# FULL_CB_Servo_REV_C.net
KiCad netlist of a schematic drawn in Altium Designer
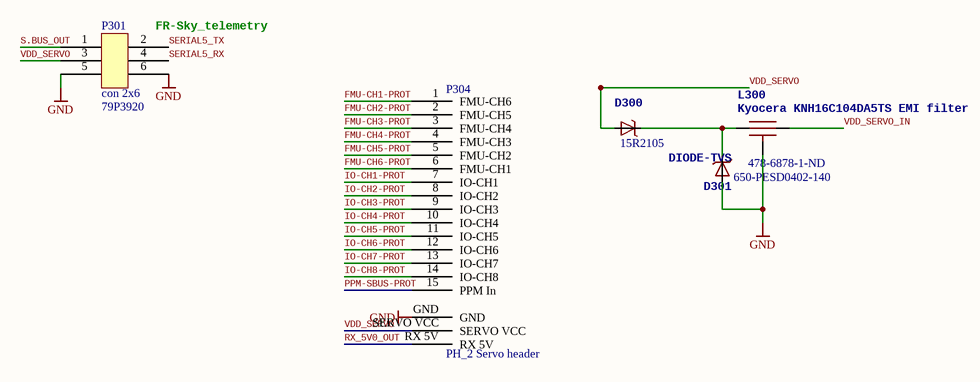
[diagram p0: FULL_CB_Servo_REV_C.SchDoc]

(export (version "E")
  (design (tool "Eeschema 10.0.6"))
  (components
    (comp (ref "D300")
      (value "MSS1P4-M3")
      (footprint "MICROSMP")
      (description "Diode, Schottky, 40V, 1A, MicroSMP, SMD")
      (fields (field (name "SUPPLIER PART NUMBER 1") "15R2105"))
      (libsource (lib "CB_REV_C") (part "DIODE-SCHOTTKY_MSMP"))
    )
    (comp (ref "D301")
      (value "DIODE-TVS")
      (footprint "0402-TVS")
      (description "Diode, TVS, 14VWM, 40VC, 0402, SMD")
      (fields (field (name "SUPPLIER PART NUMBER 1") "650-PESD0402-140"))
      (libsource (lib "CB_REV_C") (part "DIODE-TVS"))
    )
    (comp (ref "L300")
      (value "Kyocera KNH16C104DA5TS EMI filter")
      (footprint "KYOCERA-KNH16-DA")
      (description "Capacitor, Filter, 0.1uF, 25V, 2A, 0603, SMD")
      (fields (field (name "SUPPLIER PART NUMBER 1") "478-6878-1-ND"))
      (libsource (lib "CB_REV_C") (part "KNH16C104DA5TS"))
    )
    (comp (ref "P301")
      (value "con 2x6")
      (footprint "TSW-103-07-G-D")
      (description "Connector, Header, 6Pos, 2.54MM, Vert, THT, Au")
      (fields (field (name "SUPPLIER PART NUMBER 1") "79P3920"))
      (libsource (lib "CB_REV_C") (part "con 2x6"))
    )
    (comp (ref "P304")
      (value "PH_2 Servo header")
      (footprint "TSW-115-08-G-T-RA")
      (description "Connector, Header, 45Pos, 2.54MM, R/A, THT, Tin")
      (libsource (lib "CB_REV_C") (part "PH_2 Servo header"))
    )
  )
  (nets
    (net (code "1") (name "/FMU-CH1-PROT") (class "Default")
      (node (ref "P304") (pin "1") (pinfunction "FMU-CH6_1") (pintype "passive"))
    )
    (net (code "2") (name "/FMU-CH2-PROT") (class "Default")
      (node (ref "P304") (pin "2") (pinfunction "FMU-CH5_2") (pintype "passive"))
    )
    (net (code "3") (name "/FMU-CH3-PROT") (class "Default")
      (node (ref "P304") (pin "3") (pinfunction "FMU-CH4_3") (pintype "passive"))
    )
    (net (code "4") (name "/FMU-CH4-PROT") (class "Default")
      (node (ref "P304") (pin "4") (pinfunction "FMU-CH3_4") (pintype "passive"))
    )
    (net (code "5") (name "/FMU-CH5-PROT") (class "Default")
      (node (ref "P304") (pin "5") (pinfunction "FMU-CH2_5") (pintype "passive"))
    )
    (net (code "6") (name "/FMU-CH6-PROT") (class "Default")
      (node (ref "P304") (pin "6") (pinfunction "FMU-CH1_6") (pintype "passive"))
    )
    (net (code "7") (name "/IO-CH1-PROT") (class "Default")
      (node (ref "P304") (pin "7") (pinfunction "IO-CH1_7") (pintype "passive"))
    )
    (net (code "8") (name "/IO-CH2-PROT") (class "Default")
      (node (ref "P304") (pin "8") (pinfunction "IO-CH2_8") (pintype "passive"))
    )
    (net (code "9") (name "/IO-CH3-PROT") (class "Default")
      (node (ref "P304") (pin "9") (pinfunction "IO-CH3_9") (pintype "passive"))
    )
    (net (code "10") (name "/IO-CH4-PROT") (class "Default")
      (node (ref "P304") (pin "10") (pinfunction "IO-CH4_10") (pintype "passive"))
    )
    (net (code "11") (name "/IO-CH5-PROT") (class "Default")
      (node (ref "P304") (pin "11") (pinfunction "IO-CH5_11") (pintype "passive"))
    )
    (net (code "12") (name "/IO-CH6-PROT") (class "Default")
      (node (ref "P304") (pin "12") (pinfunction "IO-CH6_12") (pintype "passive"))
    )
    (net (code "13") (name "/IO-CH7-PROT") (class "Default")
      (node (ref "P304") (pin "13") (pinfunction "IO-CH7_13") (pintype "passive"))
    )
    (net (code "14") (name "/IO-CH8-PROT") (class "Default")
      (node (ref "P304") (pin "14") (pinfunction "IO-CH8_14") (pintype "passive"))
    )
    (net (code "15") (name "/PPM-SBUS-PROT") (class "Default")
      (node (ref "P304") (pin "15") (pinfunction "PPM_In_15") (pintype "passive"))
    )
    (net (code "16") (name "/RX_5V0_OUT") (class "Default")
      (node (ref "P304") (pin "RX_5V") (pinfunction "RX_5V_RX_5V") (pintype "passive"))
    )
    (net (code "17") (name "/S.BUS_OUT") (class "Default")
      (node (ref "P301") (pin "1") (pinfunction "1_1") (pintype "passive"))
    )
    (net (code "18") (name "/SERIAL5_RX") (class "Default")
      (node (ref "P301") (pin "4") (pinfunction "4_4") (pintype "passive"))
    )
    (net (code "19") (name "/SERIAL5_TX") (class "Default")
      (node (ref "P301") (pin "2") (pinfunction "2_2") (pintype "passive"))
    )
    (net (code "20") (name "/VDD_SERVO") (class "Default")
      (node (ref "D300") (pin "ANODE") (pinfunction "A_ANODE") (pintype "passive"))
      (node (ref "P301") (pin "3") (pinfunction "3_3") (pintype "passive"))
      (node (ref "P304") (pin "SERVO_VCC") (pinfunction "SERVO_VCC_SERVO_VCC") (pintype "passive"))
    )
    (net (code "21") (name "/VDD_SERVO_IN") (class "Default")
      (node (ref "L300") (pin "P$2") (pinfunction "P$2_P$2") (pintype "passive"))
    )
    (net (code "22") (name "GND") (class "Default")
      (node (ref "D301") (pin "A") (pinfunction "A_A") (pintype "passive"))
      (node (ref "L300") (pin "GND") (pinfunction "GND_GND") (pintype "passive"))
      (node (ref "P301") (pin "5") (pinfunction "5_5") (pintype "passive"))
      (node (ref "P301") (pin "6") (pinfunction "6_6") (pintype "passive"))
      (node (ref "P304") (pin "GND") (pinfunction "GND_GND") (pintype "passive"))
    )
    (net (code "23") (name "Net-(D300-C)") (class "Default")
      (node (ref "D300") (pin "CATHODE") (pinfunction "C_CATHODE") (pintype "passive"))
      (node (ref "D301") (pin "C") (pinfunction "C_C") (pintype "passive"))
      (node (ref "L300") (pin "P$1") (pinfunction "P$1_P$1") (pintype "passive"))
    )
  )
)
